# 08_USB_Type-C_DFP_DP_ALT_buttom.net
KiCad netlist of a schematic drawn in Altium Designer
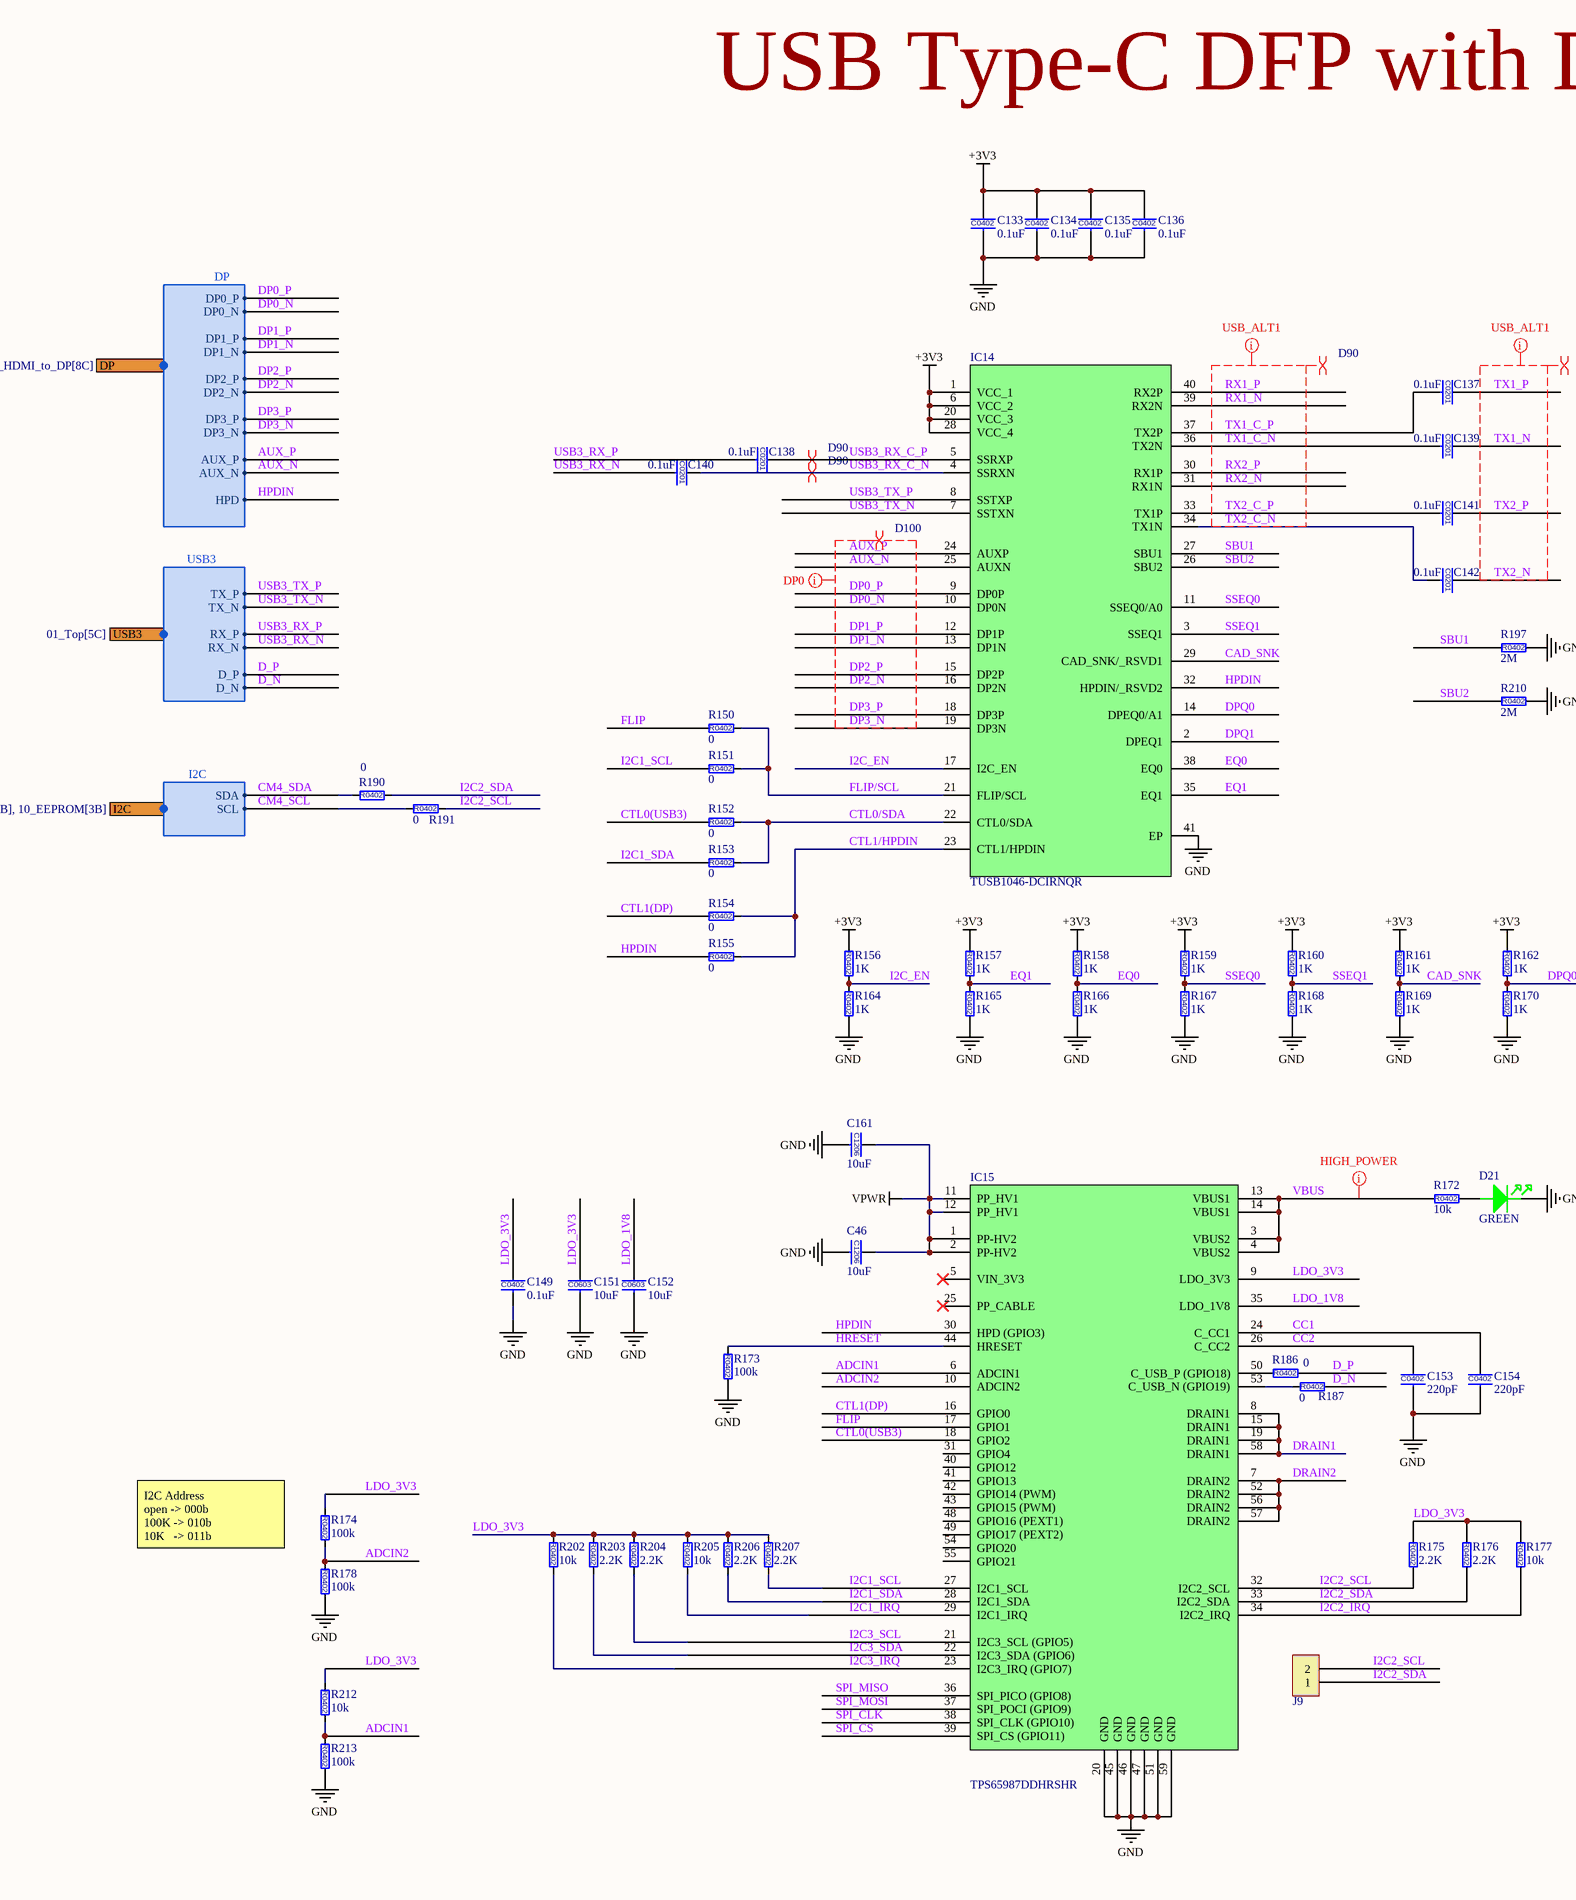
[diagram p0: 08_USB_Type-C_DFP_DP_ALT_buttom.SchDoc, left]
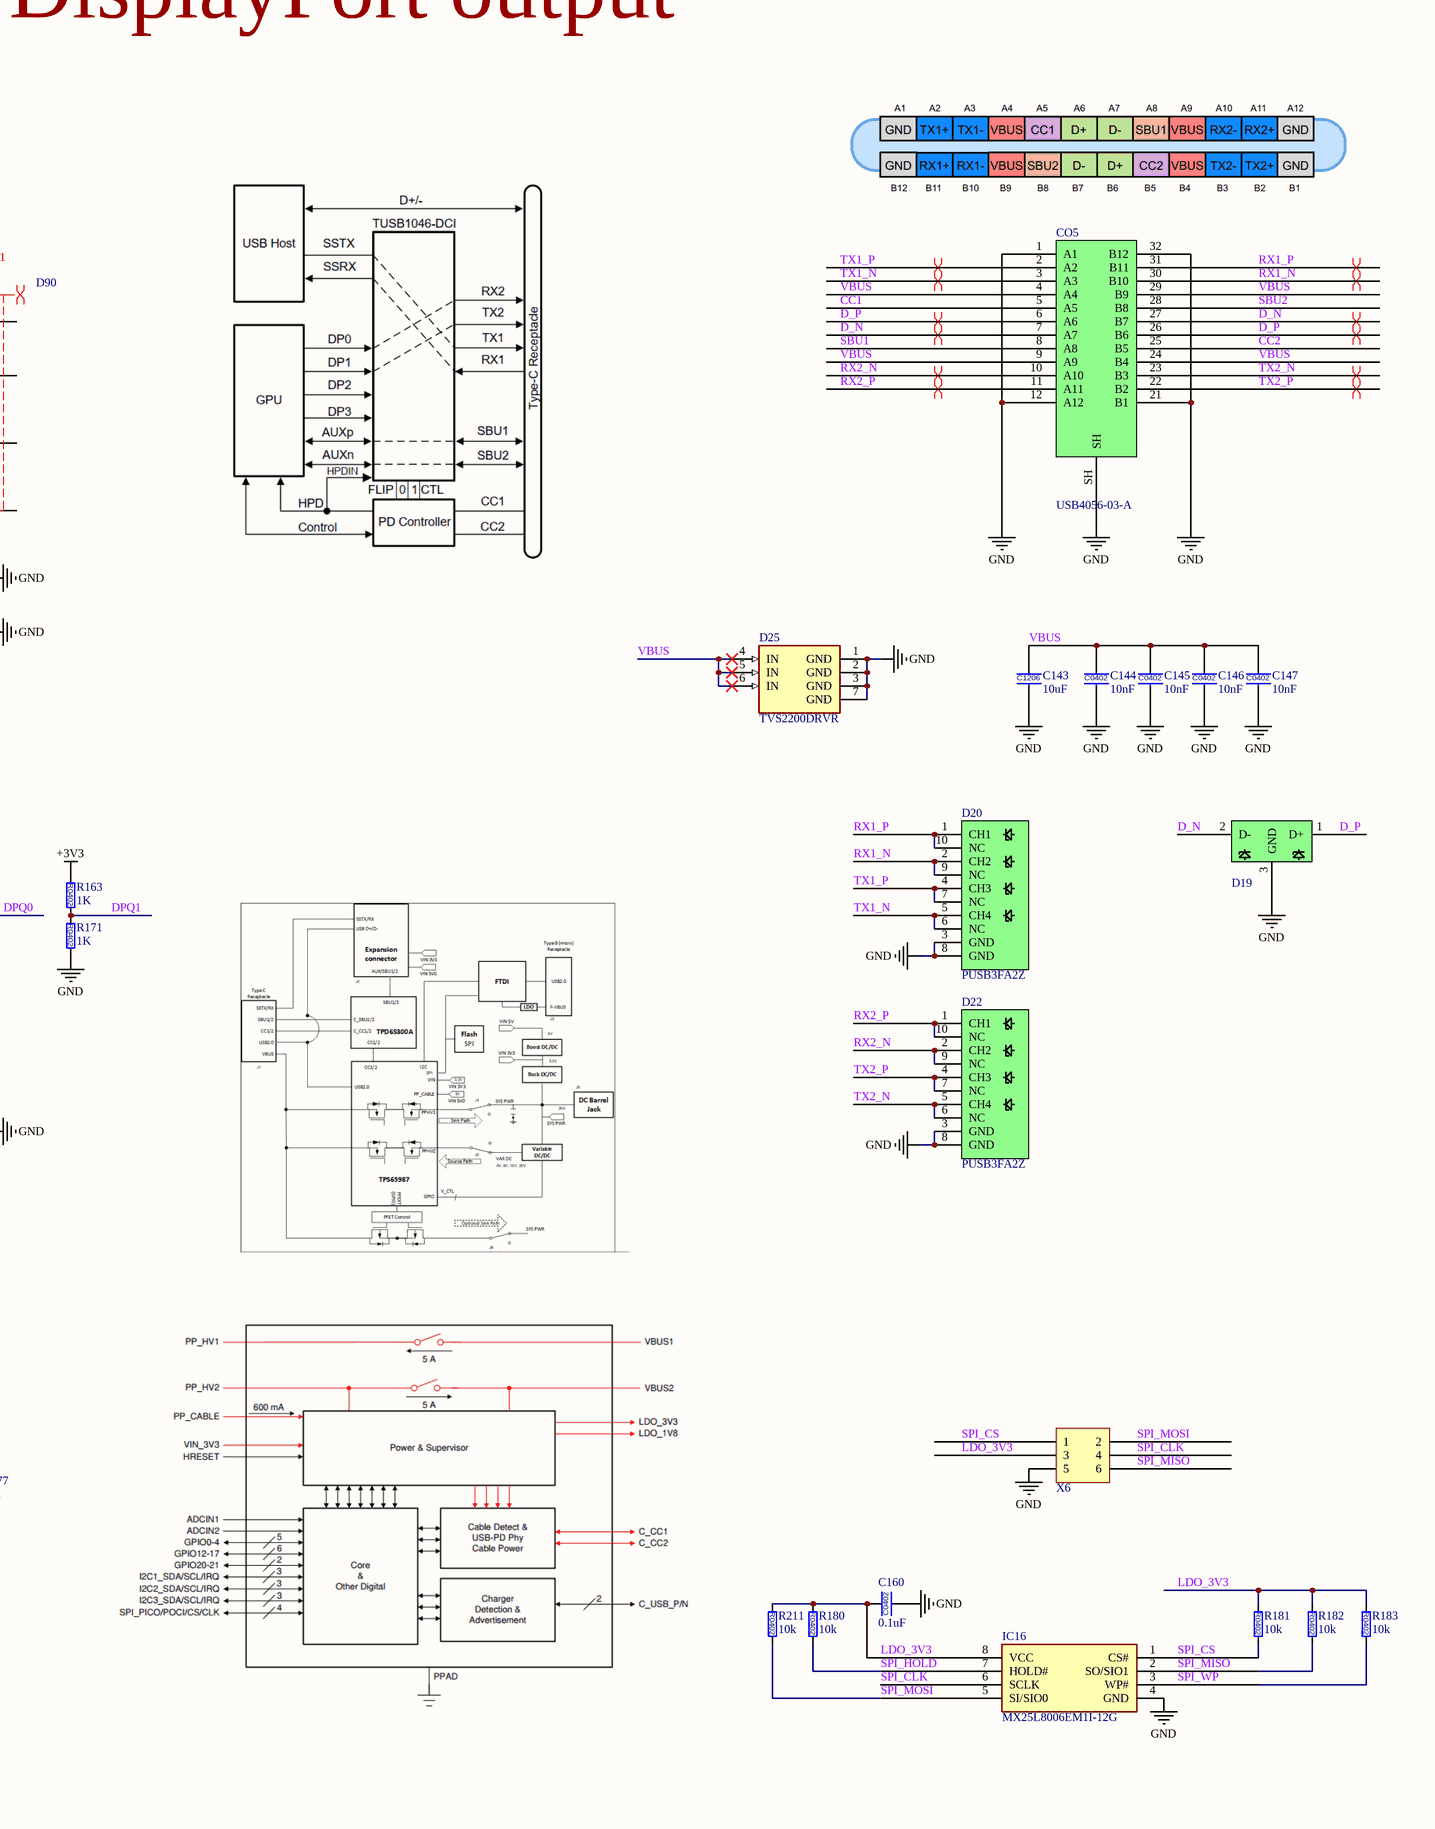
[diagram p1: 08_USB_Type-C_DFP_DP_ALT_buttom.SchDoc, right]

(export (version "E")
  (design (tool "Eeschema 10.0.6"))
  (components
    (comp (ref "C46")
      (value "10uF")
      (footprint "C1206")
      (description "CAP CER  10uF 10% 50V X5R 1206")
      (fields
        (field (name "MANUFACTURER") "KYOCERA AVX")
        (field (name "MANUFACTURER PART NUMBER") "12065D106KAT4A")
      )
      (libsource (lib "Capacitor") (part "12065D106KAT4A"))
    )
    (comp (ref "C133")
      (value "0.1uF")
      (footprint "C0402")
      (description "CAP CER  0.1uF 10% 25V X5R 0402")
      (fields
        (field (name "MANUFACTURER") "AVX Corporation")
        (field (name "MANUFACTURER PART NUMBER") "04023D104KAT2A")
      )
      (libsource (lib "Capacitor") (part "04023D104KAT2A"))
    )
    (comp (ref "C134")
      (value "0.1uF")
      (footprint "C0402")
      (description "CAP CER  0.1uF 10% 25V X5R 0402")
      (fields
        (field (name "MANUFACTURER") "AVX Corporation")
        (field (name "MANUFACTURER PART NUMBER") "04023D104KAT2A")
      )
      (libsource (lib "Capacitor") (part "04023D104KAT2A"))
    )
    (comp (ref "C135")
      (value "0.1uF")
      (footprint "C0402")
      (description "CAP CER  0.1uF 10% 25V X5R 0402")
      (fields
        (field (name "MANUFACTURER") "AVX Corporation")
        (field (name "MANUFACTURER PART NUMBER") "04023D104KAT2A")
      )
      (libsource (lib "Capacitor") (part "04023D104KAT2A"))
    )
    (comp (ref "C136")
      (value "0.1uF")
      (footprint "C0402")
      (description "CAP CER  0.1uF 10% 25V X5R 0402")
      (fields
        (field (name "MANUFACTURER") "AVX Corporation")
        (field (name "MANUFACTURER PART NUMBER") "04023D104KAT2A")
      )
      (libsource (lib "Capacitor") (part "04023D104KAT2A"))
    )
    (comp (ref "C137")
      (value "0.1uF")
      (footprint "C0201")
      (description "CAP CER  0.1uF 10% 6.3V X5R 0201")
      (fields
        (field (name "MANUFACTURER") "AVX Corporation")
        (field (name "MANUFACTURER PART NUMBER") "02016D104KAT")
      )
      (libsource (lib "Capacitor") (part "02016D104KAT"))
    )
    (comp (ref "C138")
      (value "0.1uF")
      (footprint "C0201")
      (description "CAP CER  0.1uF 10% 6.3V X5R 0201")
      (fields
        (field (name "MANUFACTURER") "AVX Corporation")
        (field (name "MANUFACTURER PART NUMBER") "02016D104KAT")
      )
      (libsource (lib "Capacitor") (part "02016D104KAT"))
    )
    (comp (ref "C139")
      (value "0.1uF")
      (footprint "C0201")
      (description "CAP CER  0.1uF 10% 6.3V X5R 0201")
      (fields
        (field (name "MANUFACTURER") "AVX Corporation")
        (field (name "MANUFACTURER PART NUMBER") "02016D104KAT")
      )
      (libsource (lib "Capacitor") (part "02016D104KAT"))
    )
    (comp (ref "C140")
      (value "0.1uF")
      (footprint "C0201")
      (description "CAP CER  0.1uF 10% 6.3V X5R 0201")
      (fields
        (field (name "MANUFACTURER") "AVX Corporation")
        (field (name "MANUFACTURER PART NUMBER") "02016D104KAT")
      )
      (libsource (lib "Capacitor") (part "02016D104KAT"))
    )
    (comp (ref "C141")
      (value "0.1uF")
      (footprint "C0201")
      (description "CAP CER  0.1uF 10% 6.3V X5R 0201")
      (fields
        (field (name "MANUFACTURER") "AVX Corporation")
        (field (name "MANUFACTURER PART NUMBER") "02016D104KAT")
      )
      (libsource (lib "Capacitor") (part "02016D104KAT"))
    )
    (comp (ref "C142")
      (value "0.1uF")
      (footprint "C0201")
      (description "CAP CER  0.1uF 10% 6.3V X5R 0201")
      (fields
        (field (name "MANUFACTURER") "AVX Corporation")
        (field (name "MANUFACTURER PART NUMBER") "02016D104KAT")
      )
      (libsource (lib "Capacitor") (part "02016D104KAT"))
    )
    (comp (ref "C143")
      (value "10uF")
      (footprint "C1206")
      (description "CAP CER  10uF 10% 50V X5R 1206")
      (fields
        (field (name "MANUFACTURER") "KYOCERA AVX")
        (field (name "MANUFACTURER PART NUMBER") "12065D106KAT4A")
      )
      (libsource (lib "Capacitor") (part "12065D106KAT4A"))
    )
    (comp (ref "C144")
      (value "10nF")
      (footprint "C0402")
      (description "CAP CER 10nF 5% 50V X7R 0402")
      (fields
        (field (name "MANUFACTURER") "KYOCERA AVX")
        (field (name "MANUFACTURER PART NUMBER") "04025C103JAT2A")
      )
      (libsource (lib "Capacitor") (part "04025C103JAT2A"))
    )
    (comp (ref "C145")
      (value "10nF")
      (footprint "C0402")
      (description "CAP CER 10nF 5% 50V X7R 0402")
      (fields
        (field (name "MANUFACTURER") "KYOCERA AVX")
        (field (name "MANUFACTURER PART NUMBER") "04025C103JAT2A")
      )
      (libsource (lib "Capacitor") (part "04025C103JAT2A"))
    )
    (comp (ref "C146")
      (value "10nF")
      (footprint "C0402")
      (description "CAP CER 10nF 5% 50V X7R 0402")
      (fields
        (field (name "MANUFACTURER") "KYOCERA AVX")
        (field (name "MANUFACTURER PART NUMBER") "04025C103JAT2A")
      )
      (libsource (lib "Capacitor") (part "04025C103JAT2A"))
    )
    (comp (ref "C147")
      (value "10nF")
      (footprint "C0402")
      (description "CAP CER 10nF 5% 50V X7R 0402")
      (fields
        (field (name "MANUFACTURER") "KYOCERA AVX")
        (field (name "MANUFACTURER PART NUMBER") "04025C103JAT2A")
      )
      (libsource (lib "Capacitor") (part "04025C103JAT2A"))
    )
    (comp (ref "C149")
      (value "0.1uF")
      (footprint "C0402")
      (description "CAP CER  0.1uF 10% 25V X5R 0402")
      (fields
        (field (name "MANUFACTURER") "AVX Corporation")
        (field (name "MANUFACTURER PART NUMBER") "04023D104KAT2A")
      )
      (libsource (lib "Capacitor") (part "04023D104KAT2A"))
    )
    (comp (ref "C151")
      (value "10uF")
      (footprint "C0603")
      (description "CAP CER 10uF 10% 10V X5R 0603")
      (fields
        (field (name "MANUFACTURER") "KYOCERA AVX")
        (field (name "MANUFACTURER PART NUMBER") "0603ZD106KAT2A")
      )
      (libsource (lib "Capacitor") (part "0603ZD106KAT2A"))
    )
    (comp (ref "C152")
      (value "10uF")
      (footprint "C0603")
      (description "CAP CER 10uF 10% 10V X5R 0603")
      (fields
        (field (name "MANUFACTURER") "KYOCERA AVX")
        (field (name "MANUFACTURER PART NUMBER") "0603ZD106KAT2A")
      )
      (libsource (lib "Capacitor") (part "0603ZD106KAT2A"))
    )
    (comp (ref "C153")
      (value "220pF")
      (footprint "C0402")
      (description "CAP CER  220pF 5% 25V NP0 0402")
      (fields
        (field (name "MANUFACTURER") "KYOCERA AVX")
        (field (name "MANUFACTURER PART NUMBER") "04023A221JAT4A")
      )
      (libsource (lib "Capacitor") (part "04023A221JAT4A"))
    )
    (comp (ref "C154")
      (value "220pF")
      (footprint "C0402")
      (description "CAP CER  220pF 5% 25V NP0 0402")
      (fields
        (field (name "MANUFACTURER") "KYOCERA AVX")
        (field (name "MANUFACTURER PART NUMBER") "04023A221JAT4A")
      )
      (libsource (lib "Capacitor") (part "04023A221JAT4A"))
    )
    (comp (ref "C160")
      (value "0.1uF")
      (footprint "C0402")
      (description "CAP CER  0.1uF 10% 25V X5R 0402")
      (fields
        (field (name "MANUFACTURER") "AVX Corporation")
        (field (name "MANUFACTURER PART NUMBER") "04023D104KAT2A")
      )
      (libsource (lib "Capacitor") (part "04023D104KAT2A"))
    )
    (comp (ref "C161")
      (value "10uF")
      (footprint "C1206")
      (description "CAP CER  10uF 10% 50V X5R 1206")
      (fields
        (field (name "MANUFACTURER") "KYOCERA AVX")
        (field (name "MANUFACTURER PART NUMBER") "12065D106KAT4A")
      )
      (libsource (lib "Capacitor") (part "12065D106KAT4A"))
    )
    (comp (ref "CO5")
      (value "USB4056-03-A")
      (footprint "USB4056-03-A")
      (description "24 Position Hybrid Top Mount USB Type C 3.2 Gen Receptacle")
      (fields
        (field (name "PART NUMBER") "CO0030")
        (field (name "MANUFACTURER") "Global Connector Technology")
      )
      (libsource (lib "new") (part "USB4056-03-A"))
    )
    (comp (ref "D19")
      (value "TPD2EUSB30DRTR")
      (footprint "TPD2EUSB30DRTR_SOT-3")
      (fields (field (name "MANUFACTURER") "Texas Instruments"))
      (libsource (lib "new") (part "TPD2EUSB30DRTR"))
    )
    (comp (ref "D20")
      (value "PUSB3FA2Z")
      (footprint "PUSB3FA2Z_DFN_2510_10")
      (description "PUSB3FA2/SOT1176/XSON10")
      (fields (field (name "PART NUMBER") "DI0007") (field (name "MANUFACTURER") "Nexperia"))
      (libsource (lib "new") (part "PUSB3FA2Z"))
    )
    (comp (ref "D21")
      (value "GREEN")
      (footprint "LED_0603")
      (description "LED Uni-Color Yellow Green 574nm 2-Pin Chip 0603(1608Metric) T/R")
      (fields
        (field (name "MANUFACTURER") "Vishay Semiconductors")
        (field (name "MANUFACTURER PART NUMBER") "VLMG1300-GS08")
      )
      (libsource (lib "led") (part "LED_SMD_0603_GREEN"))
    )
    (comp (ref "D22")
      (value "PUSB3FA2Z")
      (footprint "PUSB3FA2Z_DFN_2510_10")
      (description "PUSB3FA2/SOT1176/XSON10")
      (fields (field (name "PART NUMBER") "DI0007") (field (name "MANUFACTURER") "Nexperia"))
      (libsource (lib "new") (part "PUSB3FA2Z"))
    )
    (comp (ref "D25")
      (value "TVS2200DRVR")
      (footprint "TVS2200D_SON_6")
      (description "22-V flat-clamp surge protection device 6-WSON -40 to 125")
      (fields
        (field (name "OCTOPART") "https://octopart.com/tvs2200drvr-texas+instruments-88217346")
        (field (name "MANUFACTURER") "Texas Instruments")
      )
      (libsource (lib "new") (part "TVS2200DRVR"))
    )
    (comp (ref "IC14")
      (value "TUSB1046-DCIRNQR")
      (footprint "TUSB1046_WQFN_40")
      (fields
        (field (name "MANUFACTURER PART NUMBER") "TUSB1046AI-DCIRNQR")
        (field (name "MOUSER PART NUMBER") "595-TUSB1046-DCIRNQR")
        (field (name "MANUFACTURER") "Texas Instruments")
      )
      (libsource (lib "new") (part "TUSB1046-DCIRNQR"))
    )
    (comp (ref "IC15")
      (value "TPS65987DDHRSHR")
      (footprint "TPS65987D_VQFN-56")
      (description "USB Type-C™ and USB PD controller with integrated power switches 56-VQFN -10 to 75")
      (fields (field (name "PART NUMBER") "IC0052") (field (name "MANUFACTURER") "Texas Instruments"))
      (libsource (lib "new") (part "TPS65987DDHRSHR"))
    )
    (comp (ref "IC16")
      (value "MX25L8006EM1I-12G")
      (footprint "SamacSys:SOIC127P600X175-8N")
      (description "NOR Flash Serial 3.3V 8M-bit 8M/4M x 1/2-bit 8ns 8-Pin SOP / IC FLASH 8MBIT 86MHZ 8SOP")
      (fields (field (name "MANUFACTURER") "Macronix"))
      (libsource (lib "new") (part "MX25L8006EM1I-12G"))
    )
    (comp (ref "J9")
      (value "PLS-2")
      (footprint "PLS-2-3D")
      (description "Pin Header 2.54MM Pitch Str, 1X2PIN, Full G/f, NY6T, 6.1MM*2.5MM*3.0MM / Bag")
      (fields
        (field (name "MANUFACTURER") "Amphenol")
        (field (name "MANUFACTURER PART NUMBER") "G800W306018EU")
      )
      (libsource (lib "Connector") (part "PLS-2"))
    )
    (comp (ref "R150")
      (value "0")
      (footprint "R0402")
      (description "RES SMD 0 ohm 1/16W R0402")
      (fields
        (field (name "MANUFACTURER") "Vishay Dale")
        (field (name "MANUFACTURER PART NUMBER") "CRCW04020000Z0")
      )
      (libsource (lib "Resistor") (part "CRCW04020000Z0"))
    )
    (comp (ref "R151")
      (value "0")
      (footprint "R0402")
      (description "RES SMD 0 ohm 1/16W R0402")
      (fields
        (field (name "MANUFACTURER") "Vishay Dale")
        (field (name "MANUFACTURER PART NUMBER") "CRCW04020000Z0")
      )
      (libsource (lib "Resistor") (part "CRCW04020000Z0"))
    )
    (comp (ref "R152")
      (value "0")
      (footprint "R0402")
      (description "RES SMD 0 ohm 1/16W R0402")
      (fields
        (field (name "MANUFACTURER") "Vishay Dale")
        (field (name "MANUFACTURER PART NUMBER") "CRCW04020000Z0")
      )
      (libsource (lib "Resistor") (part "CRCW04020000Z0"))
    )
    (comp (ref "R153")
      (value "0")
      (footprint "R0402")
      (description "RES SMD 0 ohm 1/16W R0402")
      (fields
        (field (name "MANUFACTURER") "Vishay Dale")
        (field (name "MANUFACTURER PART NUMBER") "CRCW04020000Z0")
      )
      (libsource (lib "Resistor") (part "CRCW04020000Z0"))
    )
    (comp (ref "R154")
      (value "0")
      (footprint "R0402")
      (description "RES SMD 0 ohm 1/16W R0402")
      (fields
        (field (name "MANUFACTURER") "Vishay Dale")
        (field (name "MANUFACTURER PART NUMBER") "CRCW04020000Z0")
      )
      (libsource (lib "Resistor") (part "CRCW04020000Z0"))
    )
    (comp (ref "R155")
      (value "0")
      (footprint "R0402")
      (description "RES SMD 0 ohm 1/16W R0402")
      (fields
        (field (name "MANUFACTURER") "Vishay Dale")
        (field (name "MANUFACTURER PART NUMBER") "CRCW04020000Z0")
      )
      (libsource (lib "Resistor") (part "CRCW04020000Z0"))
    )
    (comp (ref "R156")
      (value "1K")
      (footprint "R0402")
      (description "RES SMD 1K ohm 1% 1/16W R0402")
      (fields
        (field (name "MANUFACTURER") "Vishay")
        (field (name "MANUFACTURER PART NUMBER") "CRCW04021K00FKEDC")
      )
      (libsource (lib "Resistor") (part "CRCW04021K00FKEDC"))
    )
    (comp (ref "R157")
      (value "1K")
      (footprint "R0402")
      (description "RES SMD 1K ohm 1% 1/16W R0402")
      (fields
        (field (name "MANUFACTURER") "Vishay")
        (field (name "MANUFACTURER PART NUMBER") "CRCW04021K00FKEDC")
      )
      (libsource (lib "Resistor") (part "CRCW04021K00FKEDC"))
    )
    (comp (ref "R158")
      (value "1K")
      (footprint "R0402")
      (description "RES SMD 1K ohm 1% 1/16W R0402")
      (fields
        (field (name "MANUFACTURER") "Vishay")
        (field (name "MANUFACTURER PART NUMBER") "CRCW04021K00FKEDC")
      )
      (libsource (lib "Resistor") (part "CRCW04021K00FKEDC"))
    )
    (comp (ref "R159")
      (value "1K")
      (footprint "R0402")
      (description "RES SMD 1K ohm 1% 1/16W R0402")
      (fields
        (field (name "MANUFACTURER") "Vishay")
        (field (name "MANUFACTURER PART NUMBER") "CRCW04021K00FKEDC")
      )
      (libsource (lib "Resistor") (part "CRCW04021K00FKEDC"))
    )
    (comp (ref "R160")
      (value "1K")
      (footprint "R0402")
      (description "RES SMD 1K ohm 1% 1/16W R0402")
      (fields
        (field (name "MANUFACTURER") "Vishay")
        (field (name "MANUFACTURER PART NUMBER") "CRCW04021K00FKEDC")
      )
      (libsource (lib "Resistor") (part "CRCW04021K00FKEDC"))
    )
    (comp (ref "R161")
      (value "1K")
      (footprint "R0402")
      (description "RES SMD 1K ohm 1% 1/16W R0402")
      (fields
        (field (name "MANUFACTURER") "Vishay")
        (field (name "MANUFACTURER PART NUMBER") "CRCW04021K00FKEDC")
      )
      (libsource (lib "Resistor") (part "CRCW04021K00FKEDC"))
    )
    (comp (ref "R162")
      (value "1K")
      (footprint "R0402")
      (description "RES SMD 1K ohm 1% 1/16W R0402")
      (fields
        (field (name "MANUFACTURER") "Vishay")
        (field (name "MANUFACTURER PART NUMBER") "CRCW04021K00FKEDC")
      )
      (libsource (lib "Resistor") (part "CRCW04021K00FKEDC"))
    )
    (comp (ref "R163")
      (value "1K")
      (footprint "R0402")
      (description "RES SMD 1K ohm 1% 1/16W R0402")
      (fields
        (field (name "MANUFACTURER") "Vishay")
        (field (name "MANUFACTURER PART NUMBER") "CRCW04021K00FKEDC")
      )
      (libsource (lib "Resistor") (part "CRCW04021K00FKEDC"))
    )
    (comp (ref "R164")
      (value "1K")
      (footprint "R0402")
      (description "RES SMD 1K ohm 1% 1/16W R0402")
      (fields
        (field (name "MANUFACTURER") "Vishay")
        (field (name "MANUFACTURER PART NUMBER") "CRCW04021K00FKEDC")
      )
      (libsource (lib "Resistor") (part "CRCW04021K00FKEDC"))
    )
    (comp (ref "R165")
      (value "1K")
      (footprint "R0402")
      (description "RES SMD 1K ohm 1% 1/16W R0402")
      (fields
        (field (name "MANUFACTURER") "Vishay")
        (field (name "MANUFACTURER PART NUMBER") "CRCW04021K00FKEDC")
      )
      (libsource (lib "Resistor") (part "CRCW04021K00FKEDC"))
    )
    (comp (ref "R166")
      (value "1K")
      (footprint "R0402")
      (description "RES SMD 1K ohm 1% 1/16W R0402")
      (fields
        (field (name "MANUFACTURER") "Vishay")
        (field (name "MANUFACTURER PART NUMBER") "CRCW04021K00FKEDC")
      )
      (libsource (lib "Resistor") (part "CRCW04021K00FKEDC"))
    )
    (comp (ref "R167")
      (value "1K")
      (footprint "R0402")
      (description "RES SMD 1K ohm 1% 1/16W R0402")
      (fields
        (field (name "MANUFACTURER") "Vishay")
        (field (name "MANUFACTURER PART NUMBER") "CRCW04021K00FKEDC")
      )
      (libsource (lib "Resistor") (part "CRCW04021K00FKEDC"))
    )
    (comp (ref "R168")
      (value "1K")
      (footprint "R0402")
      (description "RES SMD 1K ohm 1% 1/16W R0402")
      (fields
        (field (name "MANUFACTURER") "Vishay")
        (field (name "MANUFACTURER PART NUMBER") "CRCW04021K00FKEDC")
      )
      (libsource (lib "Resistor") (part "CRCW04021K00FKEDC"))
    )
    (comp (ref "R169")
      (value "1K")
      (footprint "R0402")
      (description "RES SMD 1K ohm 1% 1/16W R0402")
      (fields
        (field (name "MANUFACTURER") "Vishay")
        (field (name "MANUFACTURER PART NUMBER") "CRCW04021K00FKEDC")
      )
      (libsource (lib "Resistor") (part "CRCW04021K00FKEDC"))
    )
    (comp (ref "R170")
      (value "1K")
      (footprint "R0402")
      (description "RES SMD 1K ohm 1% 1/16W R0402")
      (fields
        (field (name "MANUFACTURER") "Vishay")
        (field (name "MANUFACTURER PART NUMBER") "CRCW04021K00FKEDC")
      )
      (libsource (lib "Resistor") (part "CRCW04021K00FKEDC"))
    )
    (comp (ref "R171")
      (value "1K")
      (footprint "R0402")
      (description "RES SMD 1K ohm 1% 1/16W R0402")
      (fields
        (field (name "MANUFACTURER") "Vishay")
        (field (name "MANUFACTURER PART NUMBER") "CRCW04021K00FKEDC")
      )
      (libsource (lib "Resistor") (part "CRCW04021K00FKEDC"))
    )
    (comp (ref "R172")
      (value "10k")
      (footprint "R0402")
      (description "RES SMD 10K ohm 1% 1/16W R0402")
      (fields
        (field (name "MANUFACTURER") "Vishay")
        (field (name "MANUFACTURER PART NUMBER") "CRCW040210K0FK")
      )
      (libsource (lib "Resistor") (part "CRCW040210K0FK"))
    )
    (comp (ref "R173")
      (value "100k")
      (footprint "R0402")
      (description "RES SMD 100K ohm 1% 1/16W R0402")
      (fields
        (field (name "MANUFACTURER") "Vishay")
        (field (name "MANUFACTURER PART NUMBER") "CRCW0402100KFKEDC")
      )
      (libsource (lib "Resistor") (part "CRCW0402100KFKEDC"))
    )
    (comp (ref "R174")
      (value "100k")
      (footprint "R0402")
      (description "RES SMD 100K ohm 1% 1/16W R0402")
      (fields
        (field (name "MANUFACTURER") "Vishay")
        (field (name "MANUFACTURER PART NUMBER") "CRCW0402100KFKEDC")
      )
      (libsource (lib "Resistor") (part "CRCW0402100KFKEDC"))
    )
    (comp (ref "R175")
      (value "2.2K")
      (footprint "R0402")
      (description "RES SMD 2.2K ohm 1% 1/16W R0402")
      (fields
        (field (name "MANUFACTURER") "Vishay")
        (field (name "MANUFACTURER PART NUMBER") "CRCW04022K20FK")
      )
      (libsource (lib "Resistor") (part "CRCW04022K20FK"))
    )
    (comp (ref "R176")
      (value "2.2K")
      (footprint "R0402")
      (description "RES SMD 2.2K ohm 1% 1/16W R0402")
      (fields
        (field (name "MANUFACTURER") "Vishay")
        (field (name "MANUFACTURER PART NUMBER") "CRCW04022K20FK")
      )
      (libsource (lib "Resistor") (part "CRCW04022K20FK"))
    )
    (comp (ref "R177")
      (value "10k")
      (footprint "R0402")
      (description "RES SMD 10K ohm 1% 1/16W R0402")
      (fields
        (field (name "MANUFACTURER") "Vishay")
        (field (name "MANUFACTURER PART NUMBER") "CRCW040210K0FK")
      )
      (libsource (lib "Resistor") (part "CRCW040210K0FK"))
    )
    (comp (ref "R178")
      (value "100k")
      (footprint "R0402")
      (description "RES SMD 100K ohm 1% 1/16W R0402")
      (fields
        (field (name "MANUFACTURER") "Vishay")
        (field (name "MANUFACTURER PART NUMBER") "CRCW0402100KFKEDC")
      )
      (libsource (lib "Resistor") (part "CRCW0402100KFKEDC"))
    )
    (comp (ref "R180")
      (value "10k")
      (footprint "R0402")
      (description "RES SMD 10K ohm 1% 1/16W R0402")
      (fields
        (field (name "MANUFACTURER") "Vishay Dale")
        (field (name "MANUFACTURER PART NUMBER") "CRCW040210K0FK")
      )
      (libsource (lib "Resistor") (part "CRCW040210K0FK"))
    )
    (comp (ref "R181")
      (value "10k")
      (footprint "R0402")
      (description "RES SMD 10K ohm 1% 1/16W R0402")
      (fields
        (field (name "MANUFACTURER") "Vishay Dale")
        (field (name "MANUFACTURER PART NUMBER") "CRCW040210K0FK")
      )
      (libsource (lib "Resistor") (part "CRCW040210K0FK"))
    )
    (comp (ref "R182")
      (value "10k")
      (footprint "R0402")
      (description "RES SMD 10K ohm 1% 1/16W R0402")
      (fields
        (field (name "MANUFACTURER") "Vishay Dale")
        (field (name "MANUFACTURER PART NUMBER") "CRCW040210K0FK")
      )
      (libsource (lib "Resistor") (part "CRCW040210K0FK"))
    )
    (comp (ref "R183")
      (value "10k")
      (footprint "R0402")
      (description "RES SMD 10K ohm 1% 1/16W R0402")
      (fields
        (field (name "MANUFACTURER") "Vishay Dale")
        (field (name "MANUFACTURER PART NUMBER") "CRCW040210K0FK")
      )
      (libsource (lib "Resistor") (part "CRCW040210K0FK"))
    )
    (comp (ref "R186")
      (value "0")
      (footprint "R0402")
      (description "RES SMD 0 ohm 1/16W R0402")
      (fields
        (field (name "MANUFACTURER") "Vishay Dale")
        (field (name "MANUFACTURER PART NUMBER") "CRCW04020000Z0")
      )
      (libsource (lib "Resistor") (part "CRCW04020000Z0"))
    )
    (comp (ref "R187")
      (value "0")
      (footprint "R0402")
      (description "RES SMD 0 ohm 1/16W R0402")
      (fields
        (field (name "MANUFACTURER") "Vishay Dale")
        (field (name "MANUFACTURER PART NUMBER") "CRCW04020000Z0")
      )
      (libsource (lib "Resistor") (part "CRCW04020000Z0"))
    )
    (comp (ref "R190")
      (value "0")
      (footprint "R0402")
      (description "RES SMD 0 ohm 1/16W R0402")
      (fields
        (field (name "MANUFACTURER") "Vishay Dale")
        (field (name "MANUFACTURER PART NUMBER") "CRCW04020000Z0")
      )
      (libsource (lib "Resistor") (part "CRCW04020000Z0"))
    )
    (comp (ref "R191")
      (value "0")
      (footprint "R0402")
      (description "RES SMD 0 ohm 1/16W R0402")
      (fields
        (field (name "MANUFACTURER") "Vishay Dale")
        (field (name "MANUFACTURER PART NUMBER") "CRCW04020000Z0")
      )
      (libsource (lib "Resistor") (part "CRCW04020000Z0"))
    )
    (comp (ref "R197")
      (value "2M")
      (footprint "R0402")
      (description "RES SMD 2M ohm 1% 1/16W R0402")
      (fields
        (field (name "MANUFACTURER") "Vishay")
        (field (name "MANUFACTURER PART NUMBER") "CRCW04022M00FKEDC")
      )
      (libsource (lib "Resistor") (part "CRCW04022M00FKEDC"))
    )
    (comp (ref "R202")
      (value "10k")
      (footprint "R0402")
      (description "RES SMD 10K ohm 1% 1/16W R0402")
      (fields
        (field (name "MANUFACTURER") "Vishay")
        (field (name "MANUFACTURER PART NUMBER") "CRCW040210K0FK")
      )
      (libsource (lib "Resistor") (part "CRCW040210K0FK"))
    )
    (comp (ref "R203")
      (value "2.2K")
      (footprint "R0402")
      (description "RES SMD 2.2K ohm 1% 1/16W R0402")
      (fields
        (field (name "MANUFACTURER") "Vishay")
        (field (name "MANUFACTURER PART NUMBER") "CRCW04022K20FK")
      )
      (libsource (lib "Resistor") (part "CRCW04022K20FK"))
    )
    (comp (ref "R204")
      (value "2.2K")
      (footprint "R0402")
      (description "RES SMD 2.2K ohm 1% 1/16W R0402")
      (fields
        (field (name "MANUFACTURER") "Vishay")
        (field (name "MANUFACTURER PART NUMBER") "CRCW04022K20FK")
      )
      (libsource (lib "Resistor") (part "CRCW04022K20FK"))
    )
    (comp (ref "R205")
      (value "10k")
      (footprint "R0402")
      (description "RES SMD 10K ohm 1% 1/16W R0402")
      (fields
        (field (name "MANUFACTURER") "Vishay")
        (field (name "MANUFACTURER PART NUMBER") "CRCW040210K0FK")
      )
      (libsource (lib "Resistor") (part "CRCW040210K0FK"))
    )
    (comp (ref "R206")
      (value "2.2K")
      (footprint "R0402")
      (description "RES SMD 2.2K ohm 1% 1/16W R0402")
      (fields
        (field (name "MANUFACTURER") "Vishay")
        (field (name "MANUFACTURER PART NUMBER") "CRCW04022K20FK")
      )
      (libsource (lib "Resistor") (part "CRCW04022K20FK"))
    )
    (comp (ref "R207")
      (value "2.2K")
      (footprint "R0402")
      (description "RES SMD 2.2K ohm 1% 1/16W R0402")
      (fields
        (field (name "MANUFACTURER") "Vishay")
        (field (name "MANUFACTURER PART NUMBER") "CRCW04022K20FK")
      )
      (libsource (lib "Resistor") (part "CRCW04022K20FK"))
    )
    (comp (ref "R210")
      (value "2M")
      (footprint "R0402")
      (description "RES SMD 2M ohm 1% 1/16W R0402")
      (fields
        (field (name "MANUFACTURER") "Vishay")
        (field (name "MANUFACTURER PART NUMBER") "CRCW04022M00FKEDC")
      )
      (libsource (lib "Resistor") (part "CRCW04022M00FKEDC"))
    )
    (comp (ref "R211")
      (value "10k")
      (footprint "R0402")
      (description "RES SMD 10K ohm 1% 1/16W R0402")
      (fields
        (field (name "MANUFACTURER") "Vishay Dale")
        (field (name "MANUFACTURER PART NUMBER") "CRCW040210K0FK")
      )
      (libsource (lib "Resistor") (part "CRCW040210K0FK"))
    )
    (comp (ref "R212")
      (value "10k")
      (footprint "R0402")
      (description "RES SMD 10K ohm 1% 1/16W R0402")
      (fields
        (field (name "MANUFACTURER") "Vishay")
        (field (name "MANUFACTURER PART NUMBER") "CRCW040210K0FK")
      )
      (libsource (lib "Resistor") (part "CRCW040210K0FK"))
    )
    (comp (ref "R213")
      (value "100k")
      (footprint "R0402")
      (description "RES SMD 100K ohm 1% 1/16W R0402")
      (fields
        (field (name "MANUFACTURER") "Vishay")
        (field (name "MANUFACTURER PART NUMBER") "CRCW0402100KFKEDC")
      )
      (libsource (lib "Resistor") (part "CRCW0402100KFKEDC"))
    )
    (comp (ref "X6")
      (value "PBD-6")
      (footprint "PXD-6")
      (description "Conn Unshrouded Header HDR 6 POS 2.54mm Solder ST Thru-Hole Poly Bag")
      (fields
        (field (name "MANUFACTURER") "Amphenol ICC / FCI")
        (field (name "MANUFACTURER PART NUMBER") "10076801-101-06LF")
        (field (name "PUBLISHER") "Altium Limited")
      )
      (libsource (lib "Connector") (part "PBD-6"))
    )
  )
  (nets
    (net (code "4") (name "+3V3") (class "Default")
      (node (ref "C133") (pin "1") (pinfunction "1_1") (pintype "passive"))
      (node (ref "C134") (pin "1") (pinfunction "1_1") (pintype "passive"))
      (node (ref "C135") (pin "1") (pinfunction "1_1") (pintype "passive"))
      (node (ref "C136") (pin "1") (pinfunction "1_1") (pintype "passive"))
      (node (ref "IC14") (pin "1") (pinfunction "VCC_1_1") (pintype "passive"))
      (node (ref "IC14") (pin "20") (pinfunction "VCC_3_20") (pintype "passive"))
      (node (ref "IC14") (pin "28") (pinfunction "VCC_4_28") (pintype "passive"))
      (node (ref "IC14") (pin "6") (pinfunction "VCC_2_6") (pintype "passive"))
      (node (ref "R156") (pin "1") (pinfunction "1_1") (pintype "passive"))
      (node (ref "R157") (pin "1") (pinfunction "1_1") (pintype "passive"))
      (node (ref "R158") (pin "1") (pinfunction "1_1") (pintype "passive"))
      (node (ref "R159") (pin "1") (pinfunction "1_1") (pintype "passive"))
      (node (ref "R160") (pin "1") (pinfunction "1_1") (pintype "passive"))
      (node (ref "R161") (pin "1") (pinfunction "1_1") (pintype "passive"))
      (node (ref "R162") (pin "1") (pinfunction "1_1") (pintype "passive"))
      (node (ref "R163") (pin "1") (pinfunction "1_1") (pintype "passive"))
    )
    (net (code "5") (name "/ADCIN1") (class "Default")
      (node (ref "IC15") (pin "6") (pinfunction "ADCIN1_6") (pintype "passive"))
      (node (ref "R212") (pin "2") (pinfunction "2_2") (pintype "passive"))
      (node (ref "R213") (pin "1") (pinfunction "1_1") (pintype "passive"))
    )
    (net (code "6") (name "/ADCIN2") (class "Default")
      (node (ref "IC15") (pin "10") (pinfunction "ADCIN2_10") (pintype "passive"))
      (node (ref "R174") (pin "2") (pinfunction "2_2") (pintype "passive"))
      (node (ref "R178") (pin "1") (pinfunction "1_1") (pintype "passive"))
    )
    (net (code "7") (name "/AUX_N") (class "Default")
      (node (ref "IC14") (pin "25") (pinfunction "AUXN_25") (pintype "passive"))
    )
    (net (code "8") (name "/AUX_P") (class "Default")
      (node (ref "IC14") (pin "24") (pinfunction "AUXP_24") (pintype "passive"))
    )
    (net (code "9") (name "/CAD_SNK") (class "Default")
      (node (ref "IC14") (pin "29") (pinfunction "CAD_SNK/_RSVD1_29") (pintype "passive"))
      (node (ref "R161") (pin "2") (pinfunction "2_2") (pintype "passive"))
      (node (ref "R169") (pin "1") (pinfunction "1_1") (pintype "passive"))
    )
    (net (code "10") (name "/CC1") (class "Default")
      (node (ref "C154") (pin "1") (pinfunction "1_1") (pintype "passive"))
      (node (ref "CO5") (pin "5") (pinfunction "A5_5") (pintype "passive"))
      (node (ref "IC15") (pin "24") (pinfunction "C_CC1_24") (pintype "passive"))
    )
    (net (code "11") (name "/CC2") (class "Default")
      (node (ref "C153") (pin "1") (pinfunction "1_1") (pintype "passive"))
      (node (ref "CO5") (pin "25") (pinfunction "B5_25") (pintype "passive"))
      (node (ref "IC15") (pin "26") (pinfunction "C_CC2_26") (pintype "passive"))
    )
    (net (code "12") (name "/CM4_SCL") (class "Default")
      (node (ref "R191") (pin "1") (pinfunction "1_1") (pintype "passive"))
    )
    (net (code "13") (name "/CM4_SDA") (class "Default")
      (node (ref "R190") (pin "1") (pinfunction "1_1") (pintype "passive"))
    )
    (net (code "14") (name "/CTL0(USB3)") (class "Default")
      (node (ref "IC15") (pin "18") (pinfunction "GPIO2_18") (pintype "passive"))
      (node (ref "R152") (pin "1") (pinfunction "1_1") (pintype "passive"))
    )
    (net (code "15") (name "/CTL0{slash}SDA") (class "Default")
      (node (ref "IC14") (pin "22") (pinfunction "CTL0/SDA_22") (pintype "passive"))
      (node (ref "R152") (pin "2") (pinfunction "2_2") (pintype "passive"))
      (node (ref "R153") (pin "2") (pinfunction "2_2") (pintype "passive"))
    )
    (net (code "16") (name "/CTL1(DP)") (class "Default")
      (node (ref "IC15") (pin "16") (pinfunction "GPIO0_16") (pintype "passive"))
      (node (ref "R154") (pin "1") (pinfunction "1_1") (pintype "passive"))
    )
    (net (code "17") (name "/CTL1{slash}HPDIN") (class "Default")
      (node (ref "IC14") (pin "23") (pinfunction "CTL1/HPDIN_23") (pintype "passive"))
      (node (ref "R154") (pin "2") (pinfunction "2_2") (pintype "passive"))
      (node (ref "R155") (pin "2") (pinfunction "2_2") (pintype "passive"))
    )
    (net (code "18") (name "/DP0_N") (class "Default")
      (node (ref "IC14") (pin "10") (pinfunction "DP0N_10") (pintype "passive"))
    )
    (net (code "19") (name "/DP0_P") (class "Default")
      (node (ref "IC14") (pin "9") (pinfunction "DP0P_9") (pintype "passive"))
    )
    (net (code "20") (name "/DP1_N") (class "Default")
      (node (ref "IC14") (pin "13") (pinfunction "DP1N_13") (pintype "passive"))
    )
    (net (code "21") (name "/DP1_P") (class "Default")
      (node (ref "IC14") (pin "12") (pinfunction "DP1P_12") (pintype "passive"))
    )
    (net (code "22") (name "/DP2_N") (class "Default")
      (node (ref "IC14") (pin "16") (pinfunction "DP2N_16") (pintype "passive"))
    )
    (net (code "23") (name "/DP2_P") (class "Default")
      (node (ref "IC14") (pin "15") (pinfunction "DP2P_15") (pintype "passive"))
    )
    (net (code "24") (name "/DP3_N") (class "Default")
      (node (ref "IC14") (pin "19") (pinfunction "DP3N_19") (pintype "passive"))
    )
    (net (code "25") (name "/DP3_P") (class "Default")
      (node (ref "IC14") (pin "18") (pinfunction "DP3P_18") (pintype "passive"))
    )
    (net (code "26") (name "/DPQ0") (class "Default")
      (node (ref "IC14") (pin "14") (pinfunction "DPEQ0/A1_14") (pintype "passive"))
      (node (ref "R162") (pin "2") (pinfunction "2_2") (pintype "passive"))
      (node (ref "R170") (pin "1") (pinfunction "1_1") (pintype "passive"))
    )
    (net (code "27") (name "/DPQ1") (class "Default")
      (node (ref "IC14") (pin "2") (pinfunction "DPEQ1_2") (pintype "passive"))
      (node (ref "R163") (pin "2") (pinfunction "2_2") (pintype "passive"))
      (node (ref "R171") (pin "1") (pinfunction "1_1") (pintype "passive"))
    )
    (net (code "28") (name "/DRAIN1") (class "Default")
      (node (ref "IC15") (pin "15") (pinfunction "DRAIN1_15") (pintype "passive"))
      (node (ref "IC15") (pin "19") (pinfunction "DRAIN1_19") (pintype "passive"))
      (node (ref "IC15") (pin "58") (pinfunction "DRAIN1_58") (pintype "passive"))
      (node (ref "IC15") (pin "8") (pinfunction "DRAIN1_8") (pintype "passive"))
    )
    (net (code "29") (name "/DRAIN2") (class "Default")
      (node (ref "IC15") (pin "52") (pinfunction "DRAIN2_52") (pintype "passive"))
      (node (ref "IC15") (pin "56") (pinfunction "DRAIN2_56") (pintype "passive"))
      (node (ref "IC15") (pin "57") (pinfunction "DRAIN2_57") (pintype "passive"))
      (node (ref "IC15") (pin "7") (pinfunction "DRAIN2_7") (pintype "passive"))
    )
    (net (code "30") (name "/D_N") (class "Default")
      (node (ref "CO5") (pin "27") (pinfunction "B7_27") (pintype "passive"))
      (node (ref "CO5") (pin "7") (pinfunction "A7_7") (pintype "passive"))
      (node (ref "D19") (pin "2") (pinfunction "D-_2") (pintype "passive"))
      (node (ref "R187") (pin "2") (pinfunction "2_2") (pintype "passive"))
    )
    (net (code "31") (name "/D_P") (class "Default")
      (node (ref "CO5") (pin "26") (pinfunction "B6_26") (pintype "passive"))
      (node (ref "CO5") (pin "6") (pinfunction "A6_6") (pintype "passive"))
      (node (ref "D19") (pin "1") (pinfunction "D+_1") (pintype "passive"))
      (node (ref "R186") (pin "2") (pinfunction "2_2") (pintype "passive"))
    )
    (net (code "32") (name "/EQ0") (class "Default")
      (node (ref "IC14") (pin "38") (pinfunction "EQ0_38") (pintype "passive"))
      (node (ref "R158") (pin "2") (pinfunction "2_2") (pintype "passive"))
      (node (ref "R166") (pin "1") (pinfunction "1_1") (pintype "passive"))
    )
    (net (code "33") (name "/EQ1") (class "Default")
      (node (ref "IC14") (pin "35") (pinfunction "EQ1_35") (pintype "passive"))
      (node (ref "R157") (pin "2") (pinfunction "2_2") (pintype "passive"))
      (node (ref "R165") (pin "1") (pinfunction "1_1") (pintype "passive"))
    )
    (net (code "34") (name "/FLIP") (class "Default")
      (node (ref "IC15") (pin "17") (pinfunction "GPIO1_17") (pintype "passive"))
      (node (ref "R150") (pin "1") (pinfunction "1_1") (pintype "passive"))
    )
    (net (code "35") (name "/FLIP{slash}SCL") (class "Default")
      (node (ref "IC14") (pin "21") (pinfunction "FLIP/SCL_21") (pintype "passive"))
      (node (ref "R150") (pin "2") (pinfunction "2_2") (pintype "passive"))
      (node (ref "R151") (pin "2") (pinfunction "2_2") (pintype "passive"))
    )
    (net (code "36") (name "/HPDIN") (class "Default")
      (node (ref "IC14") (pin "32") (pinfunction "HPDIN/_RSVD2_32") (pintype "passive"))
      (node (ref "IC15") (pin "30") (pinfunction "HPD_(GPIO3)_30") (pintype "passive"))
      (node (ref "R155") (pin "1") (pinfunction "1_1") (pintype "passive"))
    )
    (net (code "37") (name "/HRESET") (class "Default")
      (node (ref "IC15") (pin "44") (pinfunction "HRESET_44") (pintype "passive"))
      (node (ref "R173") (pin "1") (pinfunction "1_1") (pintype "passive"))
    )
    (net (code "38") (name "/I2C1_IRQ") (class "Default")
      (node (ref "IC15") (pin "29") (pinfunction "I2C1_IRQ_29") (pintype "passive"))
      (node (ref "R205") (pin "2") (pinfunction "2_2") (pintype "passive"))
    )
    (net (code "39") (name "/I2C1_SCL") (class "Default")
      (node (ref "IC15") (pin "27") (pinfunction "I2C1_SCL_27") (pintype "passive"))
      (node (ref "R151") (pin "1") (pinfunction "1_1") (pintype "passive"))
      (node (ref "R207") (pin "2") (pinfunction "2_2") (pintype "passive"))
    )
    (net (code "40") (name "/I2C1_SDA") (class "Default")
      (node (ref "IC15") (pin "28") (pinfunction "I2C1_SDA_28") (pintype "passive"))
      (node (ref "R153") (pin "1") (pinfunction "1_1") (pintype "passive"))
      (node (ref "R206") (pin "2") (pinfunction "2_2") (pintype "passive"))
    )
    (net (code "41") (name "/I2C2_IRQ") (class "Default")
      (node (ref "IC15") (pin "34") (pinfunction "I2C2_IRQ_34") (pintype "passive"))
      (node (ref "R177") (pin "2") (pinfunction "2_2") (pintype "passive"))
    )
    (net (code "42") (name "/I2C2_SCL") (class "Default")
      (node (ref "IC15") (pin "32") (pinfunction "I2C2_SCL_32") (pintype "passive"))
      (node (ref "J9") (pin "2") (pinfunction "2_2") (pintype "passive"))
      (node (ref "R175") (pin "2") (pinfunction "2_2") (pintype "passive"))
      (node (ref "R191") (pin "2") (pinfunction "2_2") (pintype "passive"))
    )
    (net (code "43") (name "/I2C2_SDA") (class "Default")
      (node (ref "IC15") (pin "33") (pinfunction "I2C2_SDA_33") (pintype "passive"))
      (node (ref "J9") (pin "1") (pinfunction "1_1") (pintype "passive"))
      (node (ref "R176") (pin "2") (pinfunction "2_2") (pintype "passive"))
      (node (ref "R190") (pin "2") (pinfunction "2_2") (pintype "passive"))
    )
    (net (code "44") (name "/I2C3_IRQ") (class "Default")
      (node (ref "IC15") (pin "23") (pinfunction "I2C3_IRQ_(GPIO7)_23") (pintype "passive"))
      (node (ref "R202") (pin "2") (pinfunction "2_2") (pintype "passive"))
    )
    (net (code "45") (name "/I2C3_SCL") (class "Default")
      (node (ref "IC15") (pin "21") (pinfunction "I2C3_SCL_(GPIO5)_21") (pintype "passive"))
      (node (ref "R204") (pin "2") (pinfunction "2_2") (pintype "passive"))
    )
    (net (code "46") (name "/I2C3_SDA") (class "Default")
      (node (ref "IC15") (pin "22") (pinfunction "I2C3_SDA_(GPIO6)_22") (pintype "passive"))
      (node (ref "R203") (pin "2") (pinfunction "2_2") (pintype "passive"))
    )
    (net (code "47") (name "/I2C_EN") (class "Default")
      (node (ref "IC14") (pin "17") (pinfunction "I2C_EN_17") (pintype "passive"))
      (node (ref "R156") (pin "2") (pinfunction "2_2") (pintype "passive"))
      (node (ref "R164") (pin "1") (pinfunction "1_1") (pintype "passive"))
    )
    (net (code "48") (name "/LDO_1V8") (class "Default")
      (node (ref "C152") (pin "1") (pinfunction "1_1") (pintype "passive"))
      (node (ref "IC15") (pin "35") (pinfunction "LDO_1V8_35") (pintype "passive"))
    )
    (net (code "49") (name "/LDO_3V3") (class "Default")
      (node (ref "C149") (pin "1") (pinfunction "1_1") (pintype "passive"))
      (node (ref "C151") (pin "1") (pinfunction "1_1") (pintype "passive"))
      (node (ref "C160") (pin "1") (pinfunction "1_1") (pintype "passive"))
      (node (ref "IC15") (pin "9") (pinfunction "LDO_3V3_9") (pintype "passive"))
      (node (ref "IC16") (pin "8") (pinfunction "VCC_8") (pintype "passive"))
      (node (ref "R174") (pin "1") (pinfunction "1_1") (pintype "passive"))
      (node (ref "R175") (pin "1") (pinfunction "1_1") (pintype "passive"))
      (node (ref "R176") (pin "1") (pinfunction "1_1") (pintype "passive"))
      (node (ref "R177") (pin "1") (pinfunction "1_1") (pintype "passive"))
      (node (ref "R180") (pin "1") (pinfunction "1_1") (pintype "passive"))
      (node (ref "R181") (pin "1") (pinfunction "1_1") (pintype "passive"))
      (node (ref "R182") (pin "1") (pinfunction "1_1") (pintype "passive"))
      (node (ref "R183") (pin "1") (pinfunction "1_1") (pintype "passive"))
      (node (ref "R202") (pin "1") (pinfunction "1_1") (pintype "passive"))
      (node (ref "R203") (pin "1") (pinfunction "1_1") (pintype "passive"))
      (node (ref "R204") (pin "1") (pinfunction "1_1") (pintype "passive"))
      (node (ref "R205") (pin "1") (pinfunction "1_1") (pintype "passive"))
      (node (ref "R206") (pin "1") (pinfunction "1_1") (pintype "passive"))
      (node (ref "R207") (pin "1") (pinfunction "1_1") (pintype "passive"))
      (node (ref "R211") (pin "1") (pinfunction "1_1") (pintype "passive"))
      (node (ref "R212") (pin "1") (pinfunction "1_1") (pintype "passive"))
      (node (ref "X6") (pin "3") (pinfunction "3_3") (pintype "passive"))
    )
    (net (code "50") (name "/RX1_N") (class "Default")
      (node (ref "CO5") (pin "30") (pinfunction "B10_30") (pintype "passive"))
      (node (ref "D20") (pin "2") (pinfunction "CH2_2") (pintype "passive"))
      (node (ref "D20") (pin "9") (pinfunction "NC_9") (pintype "passive"))
      (node (ref "IC14") (pin "39") (pinfunction "RX2N_39") (pintype "passive"))
    )
    (net (code "51") (name "/RX1_P") (class "Default")
      (node (ref "CO5") (pin "31") (pinfunction "B11_31") (pintype "passive"))
      (node (ref "D20") (pin "1") (pinfunction "CH1_1") (pintype "passive"))
      (node (ref "D20") (pin "10") (pinfunction "NC_10") (pintype "passive"))
      (node (ref "IC14") (pin "40") (pinfunction "RX2P_40") (pintype "passive"))
    )
    (net (code "52") (name "/RX2_N") (class "Default")
      (node (ref "CO5") (pin "10") (pinfunction "A10_10") (pintype "passive"))
      (node (ref "D22") (pin "2") (pinfunction "CH2_2") (pintype "passive"))
      (node (ref "D22") (pin "9") (pinfunction "NC_9") (pintype "passive"))
      (node (ref "IC14") (pin "31") (pinfunction "RX1N_31") (pintype "passive"))
    )
    (net (code "53") (name "/RX2_P") (class "Default")
      (node (ref "CO5") (pin "11") (pinfunction "A11_11") (pintype "passive"))
      (node (ref "D22") (pin "1") (pinfunction "CH1_1") (pintype "passive"))
      (node (ref "D22") (pin "10") (pinfunction "NC_10") (pintype "passive"))
      (node (ref "IC14") (pin "30") (pinfunction "RX1P_30") (pintype "passive"))
    )
    (net (code "54") (name "/SBU1") (class "Default")
      (node (ref "CO5") (pin "8") (pinfunction "A8_8") (pintype "passive"))
      (node (ref "IC14") (pin "27") (pinfunction "SBU1_27") (pintype "passive"))
      (node (ref "R197") (pin "1") (pinfunction "1_1") (pintype "passive"))
    )
    (net (code "55") (name "/SBU2") (class "Default")
      (node (ref "CO5") (pin "28") (pinfunction "B8_28") (pintype "passive"))
      (node (ref "IC14") (pin "26") (pinfunction "SBU2_26") (pintype "passive"))
      (node (ref "R210") (pin "1") (pinfunction "1_1") (pintype "passive"))
    )
    (net (code "56") (name "/SPI_CLK") (class "Default")
      (node (ref "IC15") (pin "38") (pinfunction "SPI_CLK_(GPIO10)_38") (pintype "passive"))
      (node (ref "IC16") (pin "6") (pinfunction "SCLK_6") (pintype "passive"))
      (node (ref "X6") (pin "4") (pinfunction "4_4") (pintype "passive"))
    )
    (net (code "57") (name "/SPI_CS") (class "Default")
      (node (ref "IC15") (pin "39") (pinfunction "SPI_CS_(GPIO11)_39") (pintype "passive"))
      (node (ref "IC16") (pin "1") (pinfunction "CS#_1") (pintype "passive"))
      (node (ref "R181") (pin "2") (pinfunction "2_2") (pintype "passive"))
      (node (ref "X6") (pin "1") (pinfunction "1_1") (pintype "passive"))
    )
    (net (code "58") (name "/SPI_HOLD") (class "Default")
      (node (ref "IC16") (pin "7") (pinfunction "HOLD#_7") (pintype "passive"))
      (node (ref "R180") (pin "2") (pinfunction "2_2") (pintype "passive"))
    )
    (net (code "59") (name "/SPI_MISO") (class "Default")
      (node (ref "IC15") (pin "36") (pinfunction "SPI_PICO_(GPIO8)_36") (pintype "passive"))
      (node (ref "IC16") (pin "2") (pinfunction "SO/SIO1_2") (pintype "passive"))
      (node (ref "R182") (pin "2") (pinfunction "2_2") (pintype "passive"))
      (node (ref "X6") (pin "6") (pinfunction "6_6") (pintype "passive"))
    )
    (net (code "60") (name "/SPI_MOSI") (class "Default")
      (node (ref "IC15") (pin "37") (pinfunction "SPI_POCI_(GPIO9)_37") (pintype "passive"))
      (node (ref "IC16") (pin "5") (pinfunction "SI/SIO0_5") (pintype "passive"))
      (node (ref "R211") (pin "2") (pinfunction "2_2") (pintype "passive"))
      (node (ref "X6") (pin "2") (pinfunction "2_2") (pintype "passive"))
    )
    (net (code "61") (name "/SPI_WP") (class "Default")
      (node (ref "IC16") (pin "3") (pinfunction "WP#_3") (pintype "passive"))
      (node (ref "R183") (pin "2") (pinfunction "2_2") (pintype "passive"))
    )
    (net (code "62") (name "/SSEQ0") (class "Default")
      (node (ref "IC14") (pin "11") (pinfunction "SSEQ0/A0_11") (pintype "passive"))
      (node (ref "R159") (pin "2") (pinfunction "2_2") (pintype "passive"))
      (node (ref "R167") (pin "1") (pinfunction "1_1") (pintype "passive"))
    )
    (net (code "63") (name "/SSEQ1") (class "Default")
      (node (ref "IC14") (pin "3") (pinfunction "SSEQ1_3") (pintype "passive"))
      (node (ref "R160") (pin "2") (pinfunction "2_2") (pintype "passive"))
      (node (ref "R168") (pin "1") (pinfunction "1_1") (pintype "passive"))
    )
    (net (code "64") (name "/TX1_C_N") (class "Default")
      (node (ref "C139") (pin "2") (pinfunction "2_2") (pintype "passive"))
      (node (ref "IC14") (pin "36") (pinfunction "TX2N_36") (pintype "passive"))
    )
    (net (code "65") (name "/TX1_C_P") (class "Default")
      (node (ref "C137") (pin "2") (pinfunction "2_2") (pintype "passive"))
      (node (ref "IC14") (pin "37") (pinfunction "TX2P_37") (pintype "passive"))
    )
    (net (code "66") (name "/TX1_N") (class "Default")
      (node (ref "C139") (pin "1") (pinfunction "1_1") (pintype "passive"))
      (node (ref "CO5") (pin "3") (pinfunction "A3_3") (pintype "passive"))
      (node (ref "D20") (pin "5") (pinfunction "CH4_5") (pintype "passive"))
      (node (ref "D20") (pin "6") (pinfunction "NC_6") (pintype "passive"))
    )
    (net (code "67") (name "/TX1_P") (class "Default")
      (node (ref "C137") (pin "1") (pinfunction "1_1") (pintype "passive"))
      (node (ref "CO5") (pin "2") (pinfunction "A2_2") (pintype "passive"))
      (node (ref "D20") (pin "4") (pinfunction "CH3_4") (pintype "passive"))
      (node (ref "D20") (pin "7") (pinfunction "NC_7") (pintype "passive"))
    )
    (net (code "68") (name "/TX2_C_N") (class "Default")
      (node (ref "C142") (pin "2") (pinfunction "2_2") (pintype "passive"))
      (node (ref "IC14") (pin "34") (pinfunction "TX1N_34") (pintype "passive"))
    )
    (net (code "69") (name "/TX2_C_P") (class "Default")
      (node (ref "C141") (pin "2") (pinfunction "2_2") (pintype "passive"))
      (node (ref "IC14") (pin "33") (pinfunction "TX1P_33") (pintype "passive"))
    )
    (net (code "70") (name "/TX2_N") (class "Default")
      (node (ref "C142") (pin "1") (pinfunction "1_1") (pintype "passive"))
      (node (ref "CO5") (pin "23") (pinfunction "B3_23") (pintype "passive"))
      (node (ref "D22") (pin "5") (pinfunction "CH4_5") (pintype "passive"))
      (node (ref "D22") (pin "6") (pinfunction "NC_6") (pintype "passive"))
    )
    (net (code "71") (name "/TX2_P") (class "Default")
      (node (ref "C141") (pin "1") (pinfunction "1_1") (pintype "passive"))
      (node (ref "CO5") (pin "22") (pinfunction "B2_22") (pintype "passive"))
      (node (ref "D22") (pin "4") (pinfunction "CH3_4") (pintype "passive"))
      (node (ref "D22") (pin "7") (pinfunction "NC_7") (pintype "passive"))
    )
    (net (code "72") (name "/USB3_RX_C_N") (class "Default")
      (node (ref "C140") (pin "1") (pinfunction "1_1") (pintype "passive"))
      (node (ref "IC14") (pin "4") (pinfunction "SSRXN_4") (pintype "passive"))
    )
    (net (code "73") (name "/USB3_RX_C_P") (class "Default")
      (node (ref "C138") (pin "1") (pinfunction "1_1") (pintype "passive"))
      (node (ref "IC14") (pin "5") (pinfunction "SSRXP_5") (pintype "passive"))
    )
    (net (code "74") (name "/USB3_RX_N") (class "Default")
      (node (ref "C140") (pin "2") (pinfunction "2_2") (pintype "passive"))
    )
    (net (code "75") (name "/USB3_RX_P") (class "Default")
      (node (ref "C138") (pin "2") (pinfunction "2_2") (pintype "passive"))
    )
    (net (code "76") (name "/USB3_TX_N") (class "Default")
      (node (ref "IC14") (pin "7") (pinfunction "SSTXN_7") (pintype "passive"))
    )
    (net (code "77") (name "/USB3_TX_P") (class "Default")
      (node (ref "IC14") (pin "8") (pinfunction "SSTXP_8") (pintype "passive"))
    )
    (net (code "78") (name "/VBUS") (class "Default")
      (node (ref "C143") (pin "1") (pinfunction "1_1") (pintype "passive"))
      (node (ref "C144") (pin "1") (pinfunction "1_1") (pintype "passive"))
      (node (ref "C145") (pin "1") (pinfunction "1_1") (pintype "passive"))
      (node (ref "C146") (pin "1") (pinfunction "1_1") (pintype "passive"))
      (node (ref "C147") (pin "1") (pinfunction "1_1") (pintype "passive"))
      (node (ref "CO5") (pin "24") (pinfunction "B4_24") (pintype "passive"))
      (node (ref "CO5") (pin "29") (pinfunction "B9_29") (pintype "passive"))
      (node (ref "CO5") (pin "4") (pinfunction "A4_4") (pintype "passive"))
      (node (ref "CO5") (pin "9") (pinfunction "A9_9") (pintype "passive"))
      (node (ref "D25") (pin "4") (pinfunction "IN_4") (pintype "input"))
      (node (ref "D25") (pin "5") (pinfunction "IN_5") (pintype "input"))
      (node (ref "D25") (pin "6") (pinfunction "IN_6") (pintype "input"))
      (node (ref "IC15") (pin "13") (pinfunction "VBUS1_13") (pintype "passive"))
      (node (ref "IC15") (pin "14") (pinfunction "VBUS1_14") (pintype "passive"))
      (node (ref "IC15") (pin "3") (pinfunction "VBUS2_3") (pintype "passive"))
      (node (ref "IC15") (pin "4") (pinfunction "VBUS2_4") (pintype "passive"))
      (node (ref "R172") (pin "1") (pinfunction "1_1") (pintype "passive"))
    )
    (net (code "82") (name "GND") (class "Default")
      (node (ref "C133") (pin "2") (pinfunction "2_2") (pintype "passive"))
      (node (ref "C134") (pin "2") (pinfunction "2_2") (pintype "passive"))
      (node (ref "C135") (pin "2") (pinfunction "2_2") (pintype "passive"))
      (node (ref "C136") (pin "2") (pinfunction "2_2") (pintype "passive"))
      (node (ref "C143") (pin "2") (pinfunction "2_2") (pintype "passive"))
      (node (ref "C144") (pin "2") (pinfunction "2_2") (pintype "passive"))
      (node (ref "C145") (pin "2") (pinfunction "2_2") (pintype "passive"))
      (node (ref "C146") (pin "2") (pinfunction "2_2") (pintype "passive"))
      (node (ref "C147") (pin "2") (pinfunction "2_2") (pintype "passive"))
      (node (ref "C149") (pin "2") (pinfunction "2_2") (pintype "passive"))
      (node (ref "C151") (pin "2") (pinfunction "2_2") (pintype "passive"))
      (node (ref "C152") (pin "2") (pinfunction "2_2") (pintype "passive"))
      (node (ref "C153") (pin "2") (pinfunction "2_2") (pintype "passive"))
      (node (ref "C154") (pin "2") (pinfunction "2_2") (pintype "passive"))
      (node (ref "C160") (pin "2") (pinfunction "2_2") (pintype "passive"))
      (node (ref "C161") (pin "2") (pinfunction "2_2") (pintype "passive"))
      (node (ref "C46") (pin "2") (pinfunction "2_2") (pintype "passive"))
      (node (ref "CO5") (pin "1") (pinfunction "A1_1") (pintype "passive"))
      (node (ref "CO5") (pin "12") (pinfunction "A12_12") (pintype "passive"))
      (node (ref "CO5") (pin "21") (pinfunction "B1_21") (pintype "passive"))
      (node (ref "CO5") (pin "32") (pinfunction "B12_32") (pintype "passive"))
      (node (ref "CO5") (pin "SH") (pinfunction "SH_SH") (pintype "power_in"))
      (node (ref "D19") (pin "3") (pinfunction "GND_3") (pintype "power_in"))
      (node (ref "D20") (pin "3") (pinfunction "GND_3") (pintype "passive"))
      (node (ref "D20") (pin "8") (pinfunction "GND_8") (pintype "passive"))
      (node (ref "D21") (pin "1") (pinfunction "Cathode_1") (pintype "passive"))
      (node (ref "D22") (pin "3") (pinfunction "GND_3") (pintype "passive"))
      (node (ref "D22") (pin "8") (pinfunction "GND_8") (pintype "passive"))
      (node (ref "D25") (pin "1") (pinfunction "GND_1") (pintype "power_in"))
      (node (ref "D25") (pin "2") (pinfunction "GND_2") (pintype "power_in"))
      (node (ref "D25") (pin "3") (pinfunction "GND_3") (pintype "power_in"))
      (node (ref "D25") (pin "7") (pinfunction "GND_7") (pintype "power_in"))
      (node (ref "IC14") (pin "41") (pinfunction "EP_41") (pintype "passive"))
      (node (ref "IC15") (pin "20") (pinfunction "GND_20") (pintype "passive"))
      (node (ref "IC15") (pin "45") (pinfunction "GND_45") (pintype "passive"))
      (node (ref "IC15") (pin "46") (pinfunction "GND_46") (pintype "passive"))
      (node (ref "IC15") (pin "47") (pinfunction "GND_47") (pintype "passive"))
      (node (ref "IC15") (pin "51") (pinfunction "GND_51") (pintype "passive"))
      (node (ref "IC15") (pin "59") (pinfunction "GND_59") (pintype "passive"))
      (node (ref "IC16") (pin "4") (pinfunction "GND_4") (pintype "passive"))
      (node (ref "R164") (pin "2") (pinfunction "2_2") (pintype "passive"))
      (node (ref "R165") (pin "2") (pinfunction "2_2") (pintype "passive"))
      (node (ref "R166") (pin "2") (pinfunction "2_2") (pintype "passive"))
      (node (ref "R167") (pin "2") (pinfunction "2_2") (pintype "passive"))
      (node (ref "R168") (pin "2") (pinfunction "2_2") (pintype "passive"))
      (node (ref "R169") (pin "2") (pinfunction "2_2") (pintype "passive"))
      (node (ref "R170") (pin "2") (pinfunction "2_2") (pintype "passive"))
      (node (ref "R171") (pin "2") (pinfunction "2_2") (pintype "passive"))
      (node (ref "R173") (pin "2") (pinfunction "2_2") (pintype "passive"))
      (node (ref "R178") (pin "2") (pinfunction "2_2") (pintype "passive"))
      (node (ref "R197") (pin "2") (pinfunction "2_2") (pintype "passive"))
      (node (ref "R210") (pin "2") (pinfunction "2_2") (pintype "passive"))
      (node (ref "R213") (pin "2") (pinfunction "2_2") (pintype "passive"))
      (node (ref "X6") (pin "5") (pinfunction "5_5") (pintype "passive"))
    )
    (net (code "83") (name "Net-(D21-Anode)") (class "Default")
      (node (ref "D21") (pin "2") (pinfunction "Anode_2") (pintype "passive"))
      (node (ref "R172") (pin "2") (pinfunction "2_2") (pintype "passive"))
    )
    (net (code "84") (name "Net-(IC15-C_USB_N_(GPIO19))") (class "Default")
      (node (ref "IC15") (pin "53") (pinfunction "C_USB_N_(GPIO19)_53") (pintype "passive"))
      (node (ref "R187") (pin "1") (pinfunction "1_1") (pintype "passive"))
    )
    (net (code "85") (name "Net-(IC15-C_USB_P_(GPIO18))") (class "Default")
      (node (ref "IC15") (pin "50") (pinfunction "C_USB_P_(GPIO18)_50") (pintype "passive"))
      (node (ref "R186") (pin "1") (pinfunction "1_1") (pintype "passive"))
    )
    (net (code "86") (name "VPWR") (class "Default")
      (node (ref "C161") (pin "1") (pinfunction "1_1") (pintype "passive"))
      (node (ref "C46") (pin "1") (pinfunction "1_1") (pintype "passive"))
      (node (ref "IC15") (pin "1") (pinfunction "PP-HV2_1") (pintype "passive"))
      (node (ref "IC15") (pin "11") (pinfunction "PP_HV1_11") (pintype "passive"))
      (node (ref "IC15") (pin "12") (pinfunction "PP_HV1_12") (pintype "passive"))
      (node (ref "IC15") (pin "2") (pinfunction "PP-HV2_2") (pintype "passive"))
    )
    (net (code "87") (name "unconnected-(IC15-GPIO4-Pad31)") (class "Default")
      (node (ref "IC15") (pin "31") (pinfunction "GPIO4_31") (pintype "passive"))
    )
    (net (code "88") (name "unconnected-(IC15-GPIO12-Pad40)") (class "Default")
      (node (ref "IC15") (pin "40") (pinfunction "GPIO12_40") (pintype "passive"))
    )
    (net (code "89") (name "unconnected-(IC15-GPIO13-Pad41)") (class "Default")
      (node (ref "IC15") (pin "41") (pinfunction "GPIO13_41") (pintype "passive"))
    )
    (net (code "90") (name "unconnected-(IC15-GPIO14_(PWM)-Pad42)") (class "Default")
      (node (ref "IC15") (pin "42") (pinfunction "GPIO14_(PWM)_42") (pintype "passive"))
    )
    (net (code "91") (name "unconnected-(IC15-GPIO15_(PWM)-Pad43)") (class "Default")
      (node (ref "IC15") (pin "43") (pinfunction "GPIO15_(PWM)_43") (pintype "passive"))
    )
    (net (code "92") (name "unconnected-(IC15-GPIO16_(PEXT1)-Pad48)") (class "Default")
      (node (ref "IC15") (pin "48") (pinfunction "GPIO16_(PEXT1)_48") (pintype "passive"))
    )
    (net (code "93") (name "unconnected-(IC15-GPIO17_(PEXT2)-Pad49)") (class "Default")
      (node (ref "IC15") (pin "49") (pinfunction "GPIO17_(PEXT2)_49") (pintype "passive"))
    )
    (net (code "94") (name "unconnected-(IC15-GPIO20-Pad54)") (class "Default")
      (node (ref "IC15") (pin "54") (pinfunction "GPIO20_54") (pintype "passive"))
    )
    (net (code "95") (name "unconnected-(IC15-GPIO21-Pad55)") (class "Default")
      (node (ref "IC15") (pin "55") (pinfunction "GPIO21_55") (pintype "passive"))
    )
    (net (code "96") (name "unconnected-(IC15-PP_CABLE-Pad25)") (class "Default")
      (node (ref "IC15") (pin "25") (pinfunction "PP_CABLE_25") (pintype "passive+no_connect"))
    )
    (net (code "97") (name "unconnected-(IC15-VIN_3V3-Pad5)") (class "Default")
      (node (ref "IC15") (pin "5") (pinfunction "VIN_3V3_5") (pintype "passive+no_connect"))
    )
  )
)
